# Sheet1.net
KiCad netlist of a schematic drawn in Altium Designer
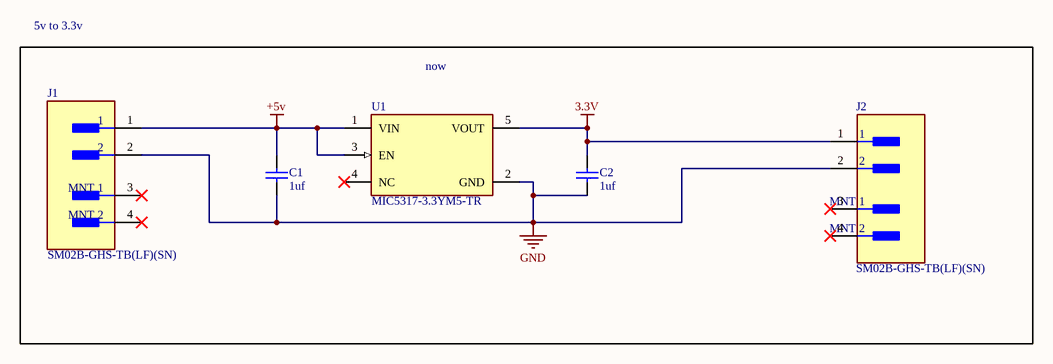
[diagram p0: Sheet1.SchDoc]

(export (version "E")
  (design (tool "Eeschema 10.0.6"))
  (components
    (comp (ref "C1")
      (value "1uf")
      (footprint "CAPC2013X100X50ML20T25")
      (fields (field (name "PART NUMBER") "C0805C105K8RACTU") (field (name "MANUFACTURER") "Kemet"))
      (libsource (lib "Altium Content Vault") (part "CAP"))
    )
    (comp (ref "C2")
      (value "1uf")
      (footprint "CAPC2013X100X50ML20T25")
      (fields (field (name "PART NUMBER") "C0805C105K8RACTU") (field (name "MANUFACTURER") "Kemet"))
      (libsource (lib "Altium Content Vault") (part "CAP"))
    )
    (comp (ref "J1")
      (value "SM02B-GHS-TB(LF)(SN)")
      (footprint "FP-SM02B-GHS-TB_LF_SN-MFG")
      (description "CONN HEADER SMD R/A 2POS 1.25MM")
      (libsource (lib "") (part "56ec3178a87b3978bdc1b3682cd516a_1"))
    )
    (comp (ref "J2")
      (value "SM02B-GHS-TB(LF)(SN)")
      (footprint "FP-SM02B-GHS-TB_LF_SN-MFG")
      (description "CONN HEADER SMD R/A 2POS 1.25MM")
      (libsource (lib "Altium Content Vault") (part "56ec3178a87b3978bdc1b3682cd516a"))
    )
    (comp (ref "U1")
      (value "MIC5317-3.3YM5-TR")
      (footprint "FP-SOT23-5LD-PL-1-MFG")
      (description "IC REG LINEAR 3.3V 150MA SOT23-5")
      (libsource (lib "Altium Content Vault") (part "0a093dae7315cdc977fd108dde87457"))
    )
  )
  (nets
    (net (code "1") (name "+5v") (class "Default")
      (node (ref "C1") (pin "2") (pinfunction "2_2") (pintype "passive"))
      (node (ref "J1") (pin "1") (pinfunction "1_1") (pintype "passive"))
      (node (ref "U1") (pin "1") (pinfunction "VIN_1") (pintype "power_in"))
      (node (ref "U1") (pin "3") (pinfunction "EN_3") (pintype "input"))
    )
    (net (code "2") (name "3.3V") (class "Default")
      (node (ref "C2") (pin "2") (pinfunction "2_2") (pintype "passive"))
      (node (ref "J2") (pin "1") (pinfunction "1_1") (pintype "passive"))
      (node (ref "U1") (pin "5") (pinfunction "VOUT_5") (pintype "power_in"))
    )
    (net (code "3") (name "GND") (class "Default")
      (node (ref "C1") (pin "1") (pinfunction "1_1") (pintype "passive"))
      (node (ref "C2") (pin "1") (pinfunction "1_1") (pintype "passive"))
      (node (ref "J1") (pin "2") (pinfunction "2_2") (pintype "passive"))
      (node (ref "J2") (pin "2") (pinfunction "2_2") (pintype "passive"))
      (node (ref "U1") (pin "2") (pinfunction "GND_2") (pintype "power_in"))
    )
    (net (code "4") (name "unconnected-(J1-MNT_1-Pad3)") (class "Default")
      (node (ref "J1") (pin "3") (pinfunction "MNT_1_3") (pintype "passive+no_connect"))
    )
    (net (code "5") (name "unconnected-(J1-MNT_2-Pad4)") (class "Default")
      (node (ref "J1") (pin "4") (pinfunction "MNT_2_4") (pintype "passive+no_connect"))
    )
    (net (code "6") (name "unconnected-(J2-MNT_1-Pad3)") (class "Default")
      (node (ref "J2") (pin "3") (pinfunction "MNT_1_3") (pintype "passive+no_connect"))
    )
    (net (code "7") (name "unconnected-(J2-MNT_2-Pad4)") (class "Default")
      (node (ref "J2") (pin "4") (pinfunction "MNT_2_4") (pintype "passive+no_connect"))
    )
    (net (code "8") (name "unconnected-(U1-NC-Pad4)") (class "Default")
      (node (ref "U1") (pin "4") (pinfunction "NC_4") (pintype "passive+no_connect"))
    )
  )
)
